# projeto_jcarlos.net
KiCad netlist of a schematic drawn in EAGLE
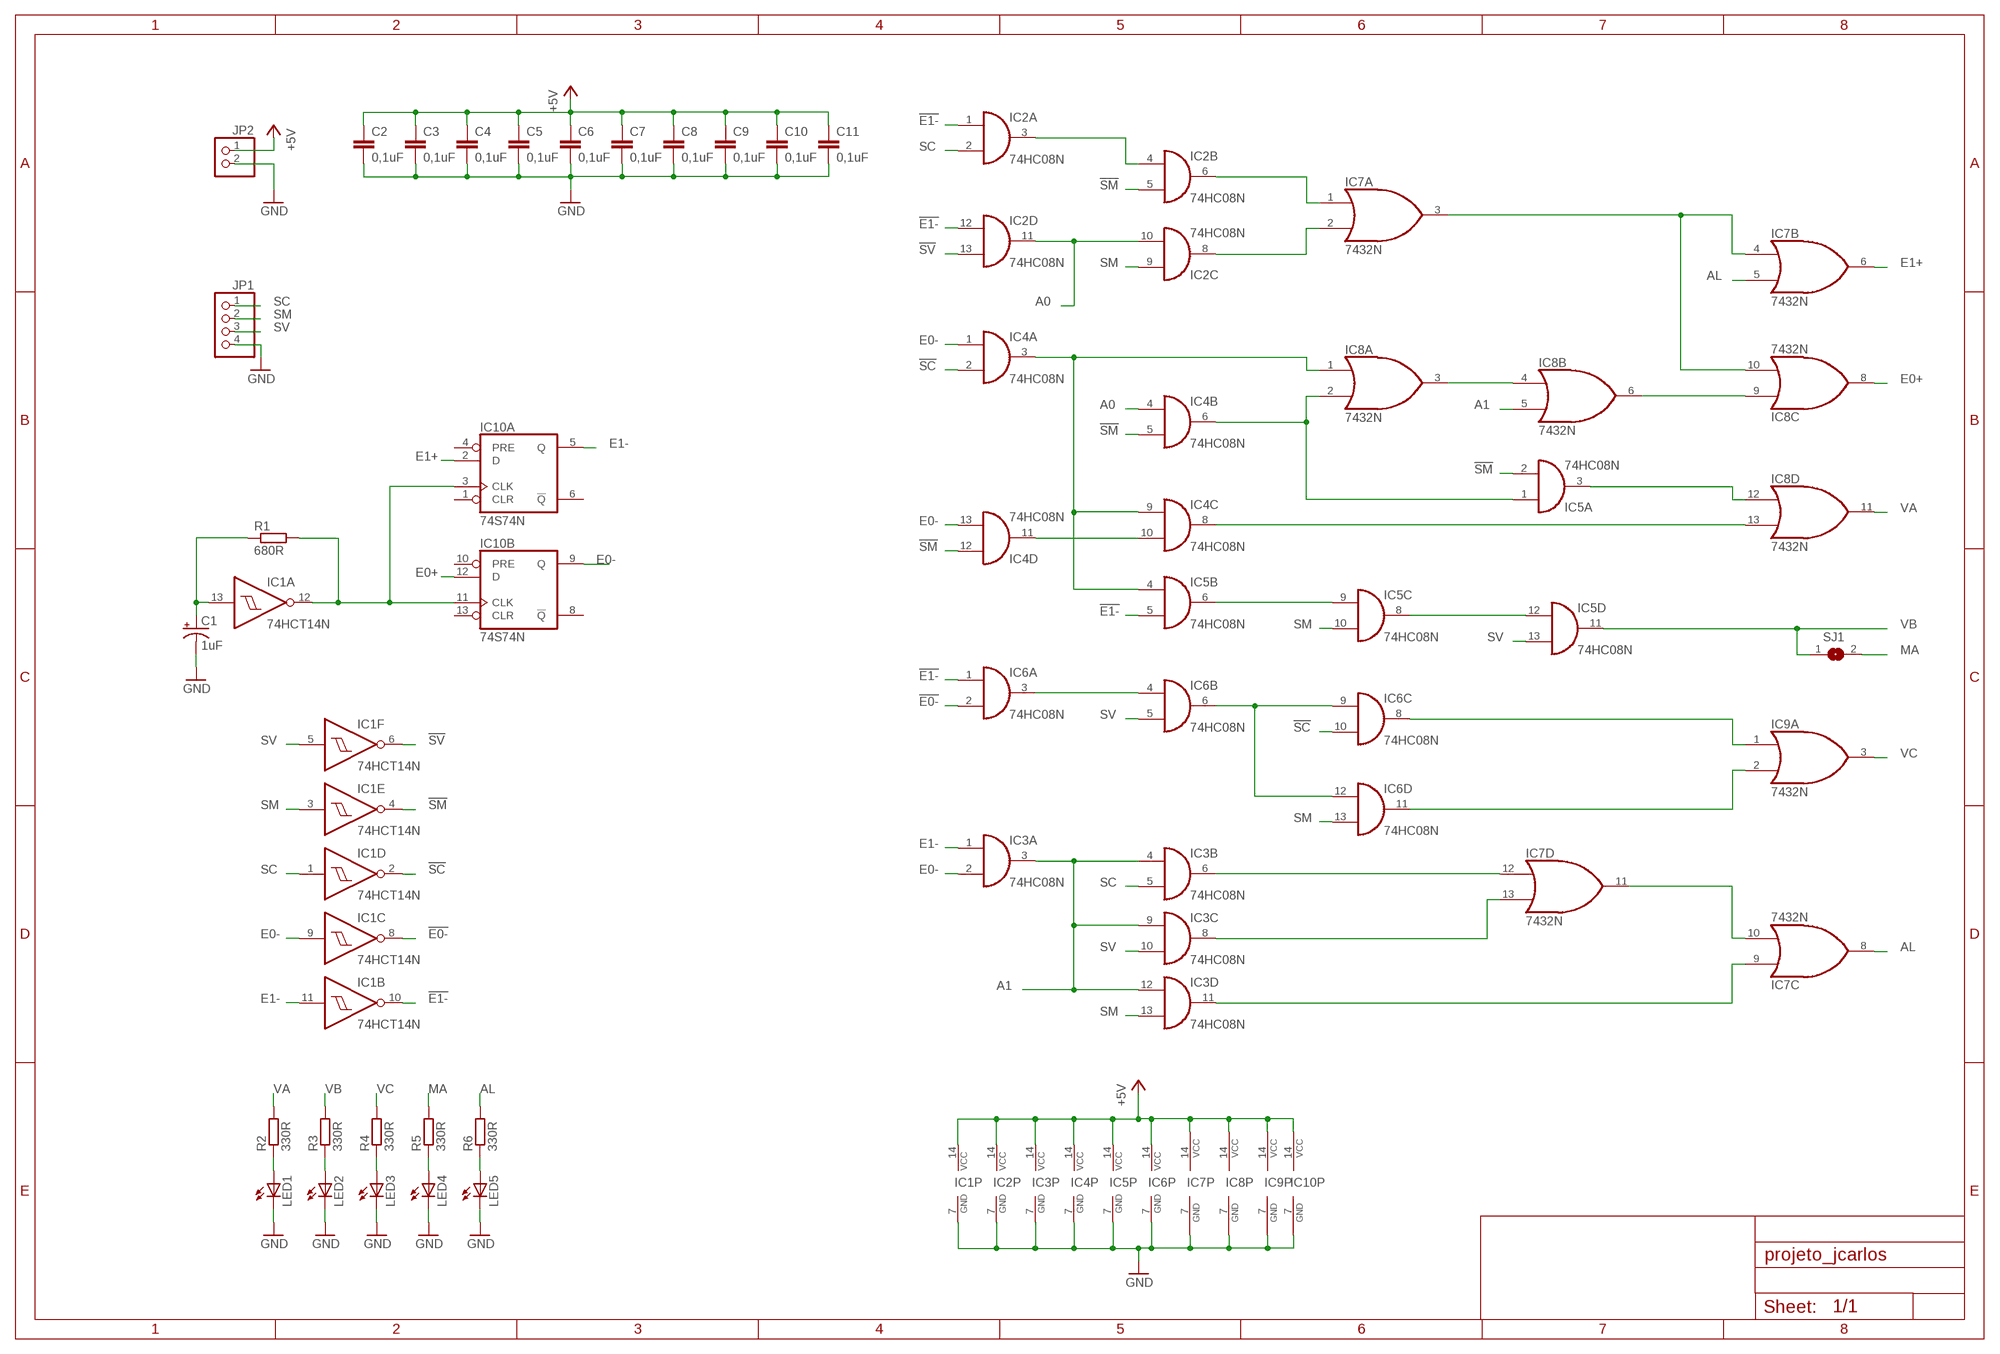
[diagram p0: schematic, sheet 1]

(export (version "E")
  (design (tool "Eeschema 10.0.6"))
  (components
    (comp (ref "C1")
      (value "1uF")
      (footprint "eagle-import:E2,5-5")
      (libsource (lib "eagle-import") (part "CPOL-USE2.5-5"))
    )
    (comp (ref "C2")
      (value "0,1uF")
      (footprint "eagle-import:C025-025X050")
      (libsource (lib "eagle-import") (part "C-EU025-025X050"))
    )
    (comp (ref "C3")
      (value "0,1uF")
      (footprint "eagle-import:C025-025X050")
      (libsource (lib "eagle-import") (part "C-EU025-025X050"))
    )
    (comp (ref "C4")
      (value "0,1uF")
      (footprint "eagle-import:C025-025X050")
      (libsource (lib "eagle-import") (part "C-EU025-025X050"))
    )
    (comp (ref "C5")
      (value "0,1uF")
      (footprint "eagle-import:C025-025X050")
      (libsource (lib "eagle-import") (part "C-EU025-025X050"))
    )
    (comp (ref "C6")
      (value "0,1uF")
      (footprint "eagle-import:C025-025X050")
      (libsource (lib "eagle-import") (part "C-EU025-025X050"))
    )
    (comp (ref "C7")
      (value "0,1uF")
      (footprint "eagle-import:C025-025X050")
      (libsource (lib "eagle-import") (part "C-EU025-025X050"))
    )
    (comp (ref "C8")
      (value "0,1uF")
      (footprint "eagle-import:C025-025X050")
      (libsource (lib "eagle-import") (part "C-EU025-025X050"))
    )
    (comp (ref "C9")
      (value "0,1uF")
      (footprint "eagle-import:C025-025X050")
      (libsource (lib "eagle-import") (part "C-EU025-025X050"))
    )
    (comp (ref "C10")
      (value "0,1uF")
      (footprint "eagle-import:C025-025X050")
      (libsource (lib "eagle-import") (part "C-EU025-025X050"))
    )
    (comp (ref "C11")
      (value "0,1uF")
      (footprint "eagle-import:C025-025X050")
      (libsource (lib "eagle-import") (part "C-EU025-025X050"))
    )
    (comp (ref "IC1")
      (value "74HCT14N")
      (footprint "eagle-import:DIL14")
      (libsource (lib "eagle-import") (part "7414NHCT"))
    )
    (comp (ref "IC2")
      (value "74HC08N")
      (footprint "eagle-import:DIL14")
      (libsource (lib "eagle-import") (part "7408NHC"))
    )
    (comp (ref "IC3")
      (value "74HC08N")
      (footprint "eagle-import:DIL14")
      (libsource (lib "eagle-import") (part "7408NHC"))
    )
    (comp (ref "IC4")
      (value "74HC08N")
      (footprint "eagle-import:DIL14")
      (libsource (lib "eagle-import") (part "7408NHC"))
    )
    (comp (ref "IC5")
      (value "74HC08N")
      (footprint "eagle-import:DIL14")
      (libsource (lib "eagle-import") (part "7408NHC"))
    )
    (comp (ref "IC6")
      (value "74HC08N")
      (footprint "eagle-import:DIL14")
      (libsource (lib "eagle-import") (part "7408NHC"))
    )
    (comp (ref "IC7")
      (value "7432N")
      (footprint "eagle-import:DIL14")
      (libsource (lib "eagle-import") (part "7432N"))
    )
    (comp (ref "IC8")
      (value "7432N")
      (footprint "eagle-import:DIL14")
      (libsource (lib "eagle-import") (part "7432N"))
    )
    (comp (ref "IC9")
      (value "7432N")
      (footprint "eagle-import:DIL14")
      (libsource (lib "eagle-import") (part "7432N"))
    )
    (comp (ref "IC10")
      (value "74S74N")
      (footprint "eagle-import:DIL14")
      (libsource (lib "eagle-import") (part "7474NS"))
    )
    (comp (ref "JP1")
      (value "PINHD-1X4")
      (footprint "eagle-import:1X04")
      (libsource (lib "eagle-import") (part "PINHD-1X4"))
    )
    (comp (ref "JP2")
      (value "PINHD-1X2")
      (footprint "eagle-import:1X02")
      (libsource (lib "eagle-import") (part "PINHD-1X2"))
    )
    (comp (ref "LED1")
      (value "LED5MM")
      (footprint "eagle-import:LED5MM")
      (libsource (lib "eagle-import") (part "LED5MM"))
    )
    (comp (ref "LED2")
      (value "LED5MM")
      (footprint "eagle-import:LED5MM")
      (libsource (lib "eagle-import") (part "LED5MM"))
    )
    (comp (ref "LED3")
      (value "LED5MM")
      (footprint "eagle-import:LED5MM")
      (libsource (lib "eagle-import") (part "LED5MM"))
    )
    (comp (ref "LED4")
      (value "LED5MM")
      (footprint "eagle-import:LED5MM")
      (libsource (lib "eagle-import") (part "LED5MM"))
    )
    (comp (ref "LED5")
      (value "LED5MM")
      (footprint "eagle-import:LED5MM")
      (libsource (lib "eagle-import") (part "LED5MM"))
    )
    (comp (ref "R1")
      (value "680R")
      (footprint "eagle-import:0204_5")
      (libsource (lib "eagle-import") (part "R-EU_0204/5"))
    )
    (comp (ref "R2")
      (value "330R")
      (footprint "eagle-import:0204_5")
      (libsource (lib "eagle-import") (part "R-EU_0204/5"))
    )
    (comp (ref "R3")
      (value "330R")
      (footprint "eagle-import:0204_5")
      (libsource (lib "eagle-import") (part "R-EU_0204/5"))
    )
    (comp (ref "R4")
      (value "330R")
      (footprint "eagle-import:0204_5")
      (libsource (lib "eagle-import") (part "R-EU_0204/5"))
    )
    (comp (ref "R5")
      (value "330R")
      (footprint "eagle-import:0204_5")
      (libsource (lib "eagle-import") (part "R-EU_0204/5"))
    )
    (comp (ref "R6")
      (value "330R")
      (footprint "eagle-import:0204_5")
      (libsource (lib "eagle-import") (part "R-EU_0204/5"))
    )
    (comp (ref "SJ1") (value "SJ") (footprint "eagle-import:SJ") (libsource (lib "eagle-import") (part "SJ")))
  )
  (nets
    (net (code "1") (name "+5V") (class "Default")
      (node (ref "C10") (pin "1") (pinfunction "1_1") (pintype "passive"))
      (node (ref "C11") (pin "1") (pinfunction "1_1") (pintype "passive"))
      (node (ref "C2") (pin "1") (pinfunction "1_1") (pintype "passive"))
      (node (ref "C3") (pin "1") (pinfunction "1_1") (pintype "passive"))
      (node (ref "C4") (pin "1") (pinfunction "1_1") (pintype "passive"))
      (node (ref "C5") (pin "1") (pinfunction "1_1") (pintype "passive"))
      (node (ref "C6") (pin "1") (pinfunction "1_1") (pintype "passive"))
      (node (ref "C7") (pin "1") (pinfunction "1_1") (pintype "passive"))
      (node (ref "C8") (pin "1") (pinfunction "1_1") (pintype "passive"))
      (node (ref "C9") (pin "1") (pinfunction "1_1") (pintype "passive"))
      (node (ref "IC1") (pin "14") (pinfunction "VCC_14") (pintype "power_in"))
      (node (ref "IC10") (pin "14") (pinfunction "VCC_14") (pintype "power_in"))
      (node (ref "IC2") (pin "14") (pinfunction "VCC_14") (pintype "power_in"))
      (node (ref "IC3") (pin "14") (pinfunction "VCC_14") (pintype "power_in"))
      (node (ref "IC4") (pin "14") (pinfunction "VCC_14") (pintype "power_in"))
      (node (ref "IC5") (pin "14") (pinfunction "VCC_14") (pintype "power_in"))
      (node (ref "IC6") (pin "14") (pinfunction "VCC_14") (pintype "power_in"))
      (node (ref "IC7") (pin "14") (pinfunction "VCC_14") (pintype "power_in"))
      (node (ref "IC8") (pin "14") (pinfunction "VCC_14") (pintype "power_in"))
      (node (ref "IC9") (pin "14") (pinfunction "VCC_14") (pintype "power_in"))
      (node (ref "JP2") (pin "1") (pinfunction "1_1") (pintype "passive"))
    )
    (net (code "2") (name "/A0") (class "Default")
      (node (ref "IC2") (pin "10") (pinfunction "I1_10") (pintype "input"))
      (node (ref "IC2") (pin "11") (pinfunction "O_11") (pintype "output"))
      (node (ref "IC4") (pin "4") (pinfunction "I0_4") (pintype "input"))
    )
    (net (code "3") (name "/A1") (class "Default")
      (node (ref "IC3") (pin "12") (pinfunction "I0_12") (pintype "input"))
      (node (ref "IC3") (pin "3") (pinfunction "O_3") (pintype "output"))
      (node (ref "IC3") (pin "4") (pinfunction "I0_4") (pintype "input"))
      (node (ref "IC3") (pin "9") (pinfunction "I0_9") (pintype "input"))
      (node (ref "IC8") (pin "5") (pinfunction "I1_5") (pintype "input"))
    )
    (net (code "4") (name "/AL") (class "Default")
      (node (ref "IC7") (pin "5") (pinfunction "I1_5") (pintype "input"))
      (node (ref "IC7") (pin "8") (pinfunction "O_8") (pintype "output"))
      (node (ref "R6") (pin "2") (pinfunction "2_2") (pintype "passive"))
    )
    (net (code "5") (name "/E0+") (class "Default")
      (node (ref "IC10") (pin "12") (pinfunction "D_12") (pintype "input"))
      (node (ref "IC8") (pin "8") (pinfunction "O_8") (pintype "output"))
    )
    (net (code "6") (name "/E0-") (class "Default")
      (node (ref "IC1") (pin "9") (pinfunction "I_9") (pintype "input"))
      (node (ref "IC10") (pin "9") (pinfunction "Q_9") (pintype "output"))
      (node (ref "IC3") (pin "2") (pinfunction "I1_2") (pintype "input"))
      (node (ref "IC4") (pin "1") (pinfunction "I0_1") (pintype "input"))
      (node (ref "IC4") (pin "13") (pinfunction "I1_13") (pintype "input"))
    )
    (net (code "7") (name "/E1+") (class "Default")
      (node (ref "IC10") (pin "2") (pinfunction "D_2") (pintype "input"))
      (node (ref "IC7") (pin "6") (pinfunction "O_6") (pintype "output"))
    )
    (net (code "8") (name "/E1-") (class "Default")
      (node (ref "IC1") (pin "11") (pinfunction "I_11") (pintype "input"))
      (node (ref "IC10") (pin "5") (pinfunction "Q_5") (pintype "output"))
      (node (ref "IC3") (pin "1") (pinfunction "I0_1") (pintype "input"))
    )
    (net (code "9") (name "/MA") (class "Default")
      (node (ref "R5") (pin "2") (pinfunction "2_2") (pintype "passive"))
      (node (ref "SJ1") (pin "2") (pinfunction "2_2") (pintype "passive"))
    )
    (net (code "10") (name "/SC") (class "Default")
      (node (ref "IC1") (pin "1") (pinfunction "I_1") (pintype "input"))
      (node (ref "IC2") (pin "2") (pinfunction "I1_2") (pintype "input"))
      (node (ref "IC3") (pin "5") (pinfunction "I1_5") (pintype "input"))
      (node (ref "JP1") (pin "1") (pinfunction "1_1") (pintype "passive"))
    )
    (net (code "11") (name "/SM") (class "Default")
      (node (ref "IC1") (pin "3") (pinfunction "I_3") (pintype "input"))
      (node (ref "IC2") (pin "9") (pinfunction "I0_9") (pintype "input"))
      (node (ref "IC3") (pin "13") (pinfunction "I1_13") (pintype "input"))
      (node (ref "IC5") (pin "10") (pinfunction "I1_10") (pintype "input"))
      (node (ref "IC6") (pin "13") (pinfunction "I1_13") (pintype "input"))
      (node (ref "JP1") (pin "2") (pinfunction "2_2") (pintype "passive"))
    )
    (net (code "12") (name "/SV") (class "Default")
      (node (ref "IC1") (pin "5") (pinfunction "I_5") (pintype "input"))
      (node (ref "IC3") (pin "10") (pinfunction "I1_10") (pintype "input"))
      (node (ref "IC5") (pin "13") (pinfunction "I1_13") (pintype "input"))
      (node (ref "IC6") (pin "5") (pinfunction "I1_5") (pintype "input"))
      (node (ref "JP1") (pin "3") (pinfunction "3_3") (pintype "passive"))
    )
    (net (code "13") (name "/VA") (class "Default")
      (node (ref "IC8") (pin "11") (pinfunction "O_11") (pintype "output"))
      (node (ref "R2") (pin "2") (pinfunction "2_2") (pintype "passive"))
    )
    (net (code "14") (name "/VB") (class "Default")
      (node (ref "IC5") (pin "11") (pinfunction "O_11") (pintype "output"))
      (node (ref "R3") (pin "2") (pinfunction "2_2") (pintype "passive"))
      (node (ref "SJ1") (pin "1") (pinfunction "1_1") (pintype "passive"))
    )
    (net (code "15") (name "/VC") (class "Default")
      (node (ref "IC9") (pin "3") (pinfunction "O_3") (pintype "output"))
      (node (ref "R4") (pin "2") (pinfunction "2_2") (pintype "passive"))
    )
    (net (code "16") (name "/~{E0-}") (class "Default")
      (node (ref "IC1") (pin "8") (pinfunction "O_8") (pintype "output"))
      (node (ref "IC6") (pin "2") (pinfunction "I1_2") (pintype "input"))
    )
    (net (code "17") (name "/~{E1-}") (class "Default")
      (node (ref "IC1") (pin "10") (pinfunction "O_10") (pintype "output"))
      (node (ref "IC2") (pin "1") (pinfunction "I0_1") (pintype "input"))
      (node (ref "IC2") (pin "12") (pinfunction "I0_12") (pintype "input"))
      (node (ref "IC5") (pin "5") (pinfunction "I1_5") (pintype "input"))
      (node (ref "IC6") (pin "1") (pinfunction "I0_1") (pintype "input"))
    )
    (net (code "18") (name "/~{SC}") (class "Default")
      (node (ref "IC1") (pin "2") (pinfunction "O_2") (pintype "output"))
      (node (ref "IC4") (pin "2") (pinfunction "I1_2") (pintype "input"))
      (node (ref "IC6") (pin "10") (pinfunction "I1_10") (pintype "input"))
    )
    (net (code "19") (name "/~{SM}") (class "Default")
      (node (ref "IC1") (pin "4") (pinfunction "O_4") (pintype "output"))
      (node (ref "IC2") (pin "5") (pinfunction "I1_5") (pintype "input"))
      (node (ref "IC4") (pin "12") (pinfunction "I0_12") (pintype "input"))
      (node (ref "IC4") (pin "5") (pinfunction "I1_5") (pintype "input"))
      (node (ref "IC5") (pin "2") (pinfunction "I1_2") (pintype "input"))
    )
    (net (code "20") (name "/~{SV}") (class "Default")
      (node (ref "IC1") (pin "6") (pinfunction "O_6") (pintype "output"))
      (node (ref "IC2") (pin "13") (pinfunction "I1_13") (pintype "input"))
    )
    (net (code "21") (name "GND") (class "Default")
      (node (ref "C1") (pin "-") (pinfunction "-_-") (pintype "passive"))
      (node (ref "C10") (pin "2") (pinfunction "2_2") (pintype "passive"))
      (node (ref "C11") (pin "2") (pinfunction "2_2") (pintype "passive"))
      (node (ref "C2") (pin "2") (pinfunction "2_2") (pintype "passive"))
      (node (ref "C3") (pin "2") (pinfunction "2_2") (pintype "passive"))
      (node (ref "C4") (pin "2") (pinfunction "2_2") (pintype "passive"))
      (node (ref "C5") (pin "2") (pinfunction "2_2") (pintype "passive"))
      (node (ref "C6") (pin "2") (pinfunction "2_2") (pintype "passive"))
      (node (ref "C7") (pin "2") (pinfunction "2_2") (pintype "passive"))
      (node (ref "C8") (pin "2") (pinfunction "2_2") (pintype "passive"))
      (node (ref "C9") (pin "2") (pinfunction "2_2") (pintype "passive"))
      (node (ref "IC1") (pin "7") (pinfunction "GND_7") (pintype "power_in"))
      (node (ref "IC10") (pin "7") (pinfunction "GND_7") (pintype "power_in"))
      (node (ref "IC2") (pin "7") (pinfunction "GND_7") (pintype "power_in"))
      (node (ref "IC3") (pin "7") (pinfunction "GND_7") (pintype "power_in"))
      (node (ref "IC4") (pin "7") (pinfunction "GND_7") (pintype "power_in"))
      (node (ref "IC5") (pin "7") (pinfunction "GND_7") (pintype "power_in"))
      (node (ref "IC6") (pin "7") (pinfunction "GND_7") (pintype "power_in"))
      (node (ref "IC7") (pin "7") (pinfunction "GND_7") (pintype "power_in"))
      (node (ref "IC8") (pin "7") (pinfunction "GND_7") (pintype "power_in"))
      (node (ref "IC9") (pin "7") (pinfunction "GND_7") (pintype "power_in"))
      (node (ref "JP1") (pin "4") (pinfunction "4_4") (pintype "passive"))
      (node (ref "JP2") (pin "2") (pinfunction "2_2") (pintype "passive"))
      (node (ref "LED1") (pin "K") (pinfunction "C_K") (pintype "passive"))
      (node (ref "LED2") (pin "K") (pinfunction "C_K") (pintype "passive"))
      (node (ref "LED3") (pin "K") (pinfunction "C_K") (pintype "passive"))
      (node (ref "LED4") (pin "K") (pinfunction "C_K") (pintype "passive"))
      (node (ref "LED5") (pin "K") (pinfunction "C_K") (pintype "passive"))
    )
    (net (code "22") (name "Net-(IC1A-I)") (class "Default")
      (node (ref "C1") (pin "+") (pinfunction "+_+") (pintype "passive"))
      (node (ref "IC1") (pin "13") (pinfunction "I_13") (pintype "input"))
      (node (ref "R1") (pin "1") (pinfunction "1_1") (pintype "passive"))
    )
    (net (code "23") (name "Net-(IC2A-O)") (class "Default")
      (node (ref "IC2") (pin "3") (pinfunction "O_3") (pintype "output"))
      (node (ref "IC2") (pin "4") (pinfunction "I0_4") (pintype "input"))
    )
    (net (code "24") (name "Net-(IC2B-O)") (class "Default")
      (node (ref "IC2") (pin "6") (pinfunction "O_6") (pintype "output"))
      (node (ref "IC7") (pin "1") (pinfunction "I0_1") (pintype "input"))
    )
    (net (code "25") (name "Net-(IC2C-O)") (class "Default")
      (node (ref "IC2") (pin "8") (pinfunction "O_8") (pintype "output"))
      (node (ref "IC7") (pin "2") (pinfunction "I1_2") (pintype "input"))
    )
    (net (code "26") (name "Net-(IC3B-O)") (class "Default")
      (node (ref "IC3") (pin "6") (pinfunction "O_6") (pintype "output"))
      (node (ref "IC7") (pin "12") (pinfunction "I0_12") (pintype "input"))
    )
    (net (code "27") (name "Net-(IC3C-O)") (class "Default")
      (node (ref "IC3") (pin "8") (pinfunction "O_8") (pintype "output"))
      (node (ref "IC7") (pin "13") (pinfunction "I1_13") (pintype "input"))
    )
    (net (code "28") (name "Net-(IC3D-O)") (class "Default")
      (node (ref "IC3") (pin "11") (pinfunction "O_11") (pintype "output"))
      (node (ref "IC7") (pin "9") (pinfunction "I0_9") (pintype "input"))
    )
    (net (code "29") (name "Net-(IC4A-O)") (class "Default")
      (node (ref "IC4") (pin "3") (pinfunction "O_3") (pintype "output"))
      (node (ref "IC4") (pin "9") (pinfunction "I0_9") (pintype "input"))
      (node (ref "IC5") (pin "4") (pinfunction "I0_4") (pintype "input"))
      (node (ref "IC8") (pin "1") (pinfunction "I0_1") (pintype "input"))
    )
    (net (code "30") (name "Net-(IC4B-O)") (class "Default")
      (node (ref "IC4") (pin "6") (pinfunction "O_6") (pintype "output"))
      (node (ref "IC5") (pin "1") (pinfunction "I0_1") (pintype "input"))
      (node (ref "IC8") (pin "2") (pinfunction "I1_2") (pintype "input"))
    )
    (net (code "31") (name "Net-(IC4C-I1)") (class "Default")
      (node (ref "IC4") (pin "10") (pinfunction "I1_10") (pintype "input"))
      (node (ref "IC4") (pin "11") (pinfunction "O_11") (pintype "output"))
    )
    (net (code "32") (name "Net-(IC4C-O)") (class "Default")
      (node (ref "IC4") (pin "8") (pinfunction "O_8") (pintype "output"))
      (node (ref "IC8") (pin "13") (pinfunction "I1_13") (pintype "input"))
    )
    (net (code "33") (name "Net-(IC5A-O)") (class "Default")
      (node (ref "IC5") (pin "3") (pinfunction "O_3") (pintype "output"))
      (node (ref "IC8") (pin "12") (pinfunction "I0_12") (pintype "input"))
    )
    (net (code "34") (name "Net-(IC5B-O)") (class "Default")
      (node (ref "IC5") (pin "6") (pinfunction "O_6") (pintype "output"))
      (node (ref "IC5") (pin "9") (pinfunction "I0_9") (pintype "input"))
    )
    (net (code "35") (name "Net-(IC5C-O)") (class "Default")
      (node (ref "IC5") (pin "12") (pinfunction "I0_12") (pintype "input"))
      (node (ref "IC5") (pin "8") (pinfunction "O_8") (pintype "output"))
    )
    (net (code "36") (name "Net-(IC6A-O)") (class "Default")
      (node (ref "IC6") (pin "3") (pinfunction "O_3") (pintype "output"))
      (node (ref "IC6") (pin "4") (pinfunction "I0_4") (pintype "input"))
    )
    (net (code "37") (name "Net-(IC6B-O)") (class "Default")
      (node (ref "IC6") (pin "12") (pinfunction "I0_12") (pintype "input"))
      (node (ref "IC6") (pin "6") (pinfunction "O_6") (pintype "output"))
      (node (ref "IC6") (pin "9") (pinfunction "I0_9") (pintype "input"))
    )
    (net (code "38") (name "Net-(IC6C-O)") (class "Default")
      (node (ref "IC6") (pin "8") (pinfunction "O_8") (pintype "output"))
      (node (ref "IC9") (pin "1") (pinfunction "I0_1") (pintype "input"))
    )
    (net (code "39") (name "Net-(IC6D-O)") (class "Default")
      (node (ref "IC6") (pin "11") (pinfunction "O_11") (pintype "output"))
      (node (ref "IC9") (pin "2") (pinfunction "I1_2") (pintype "input"))
    )
    (net (code "40") (name "Net-(IC7A-O)") (class "Default")
      (node (ref "IC7") (pin "3") (pinfunction "O_3") (pintype "output"))
      (node (ref "IC7") (pin "4") (pinfunction "I0_4") (pintype "input"))
      (node (ref "IC8") (pin "10") (pinfunction "I1_10") (pintype "input"))
    )
    (net (code "41") (name "Net-(IC7C-I1)") (class "Default")
      (node (ref "IC7") (pin "10") (pinfunction "I1_10") (pintype "input"))
      (node (ref "IC7") (pin "11") (pinfunction "O_11") (pintype "output"))
    )
    (net (code "42") (name "Net-(IC8A-O)") (class "Default")
      (node (ref "IC8") (pin "3") (pinfunction "O_3") (pintype "output"))
      (node (ref "IC8") (pin "4") (pinfunction "I0_4") (pintype "input"))
    )
    (net (code "43") (name "Net-(IC8B-O)") (class "Default")
      (node (ref "IC8") (pin "6") (pinfunction "O_6") (pintype "output"))
      (node (ref "IC8") (pin "9") (pinfunction "I0_9") (pintype "input"))
    )
    (net (code "44") (name "Net-(IC10A-CLK)") (class "Default")
      (node (ref "IC1") (pin "12") (pinfunction "O_12") (pintype "output"))
      (node (ref "IC10") (pin "11") (pinfunction "CLK_11") (pintype "input"))
      (node (ref "IC10") (pin "3") (pinfunction "CLK_3") (pintype "input"))
      (node (ref "R1") (pin "2") (pinfunction "2_2") (pintype "passive"))
    )
    (net (code "45") (name "Net-(LED1-PadA)") (class "Default")
      (node (ref "LED1") (pin "A") (pinfunction "A_A") (pintype "passive"))
      (node (ref "R2") (pin "1") (pinfunction "1_1") (pintype "passive"))
    )
    (net (code "46") (name "Net-(LED2-PadA)") (class "Default")
      (node (ref "LED2") (pin "A") (pinfunction "A_A") (pintype "passive"))
      (node (ref "R3") (pin "1") (pinfunction "1_1") (pintype "passive"))
    )
    (net (code "47") (name "Net-(LED3-PadA)") (class "Default")
      (node (ref "LED3") (pin "A") (pinfunction "A_A") (pintype "passive"))
      (node (ref "R4") (pin "1") (pinfunction "1_1") (pintype "passive"))
    )
    (net (code "48") (name "Net-(LED4-PadA)") (class "Default")
      (node (ref "LED4") (pin "A") (pinfunction "A_A") (pintype "passive"))
      (node (ref "R5") (pin "1") (pinfunction "1_1") (pintype "passive"))
    )
    (net (code "49") (name "Net-(LED5-PadA)") (class "Default")
      (node (ref "LED5") (pin "A") (pinfunction "A_A") (pintype "passive"))
      (node (ref "R6") (pin "1") (pinfunction "1_1") (pintype "passive"))
    )
    (net (code "50") (name "unconnected-(IC10A-CLR-Pad1)") (class "Default")
      (node (ref "IC10") (pin "1") (pinfunction "CLR_1") (pintype "input"))
    )
    (net (code "51") (name "unconnected-(IC10A-PRE-Pad4)") (class "Default")
      (node (ref "IC10") (pin "4") (pinfunction "PRE_4") (pintype "input"))
    )
    (net (code "52") (name "unconnected-(IC10A-~{Q}-Pad6)") (class "Default")
      (node (ref "IC10") (pin "6") (pinfunction "~{Q}_6") (pintype "output"))
    )
    (net (code "53") (name "unconnected-(IC10B-CLR-Pad13)") (class "Default")
      (node (ref "IC10") (pin "13") (pinfunction "CLR_13") (pintype "input"))
    )
    (net (code "54") (name "unconnected-(IC10B-PRE-Pad10)") (class "Default")
      (node (ref "IC10") (pin "10") (pinfunction "PRE_10") (pintype "input"))
    )
    (net (code "55") (name "unconnected-(IC10B-~{Q}-Pad8)") (class "Default")
      (node (ref "IC10") (pin "8") (pinfunction "~{Q}_8") (pintype "output"))
    )
  )
)
